# AltimeterFio.net
KiCad netlist of a schematic drawn in EAGLE
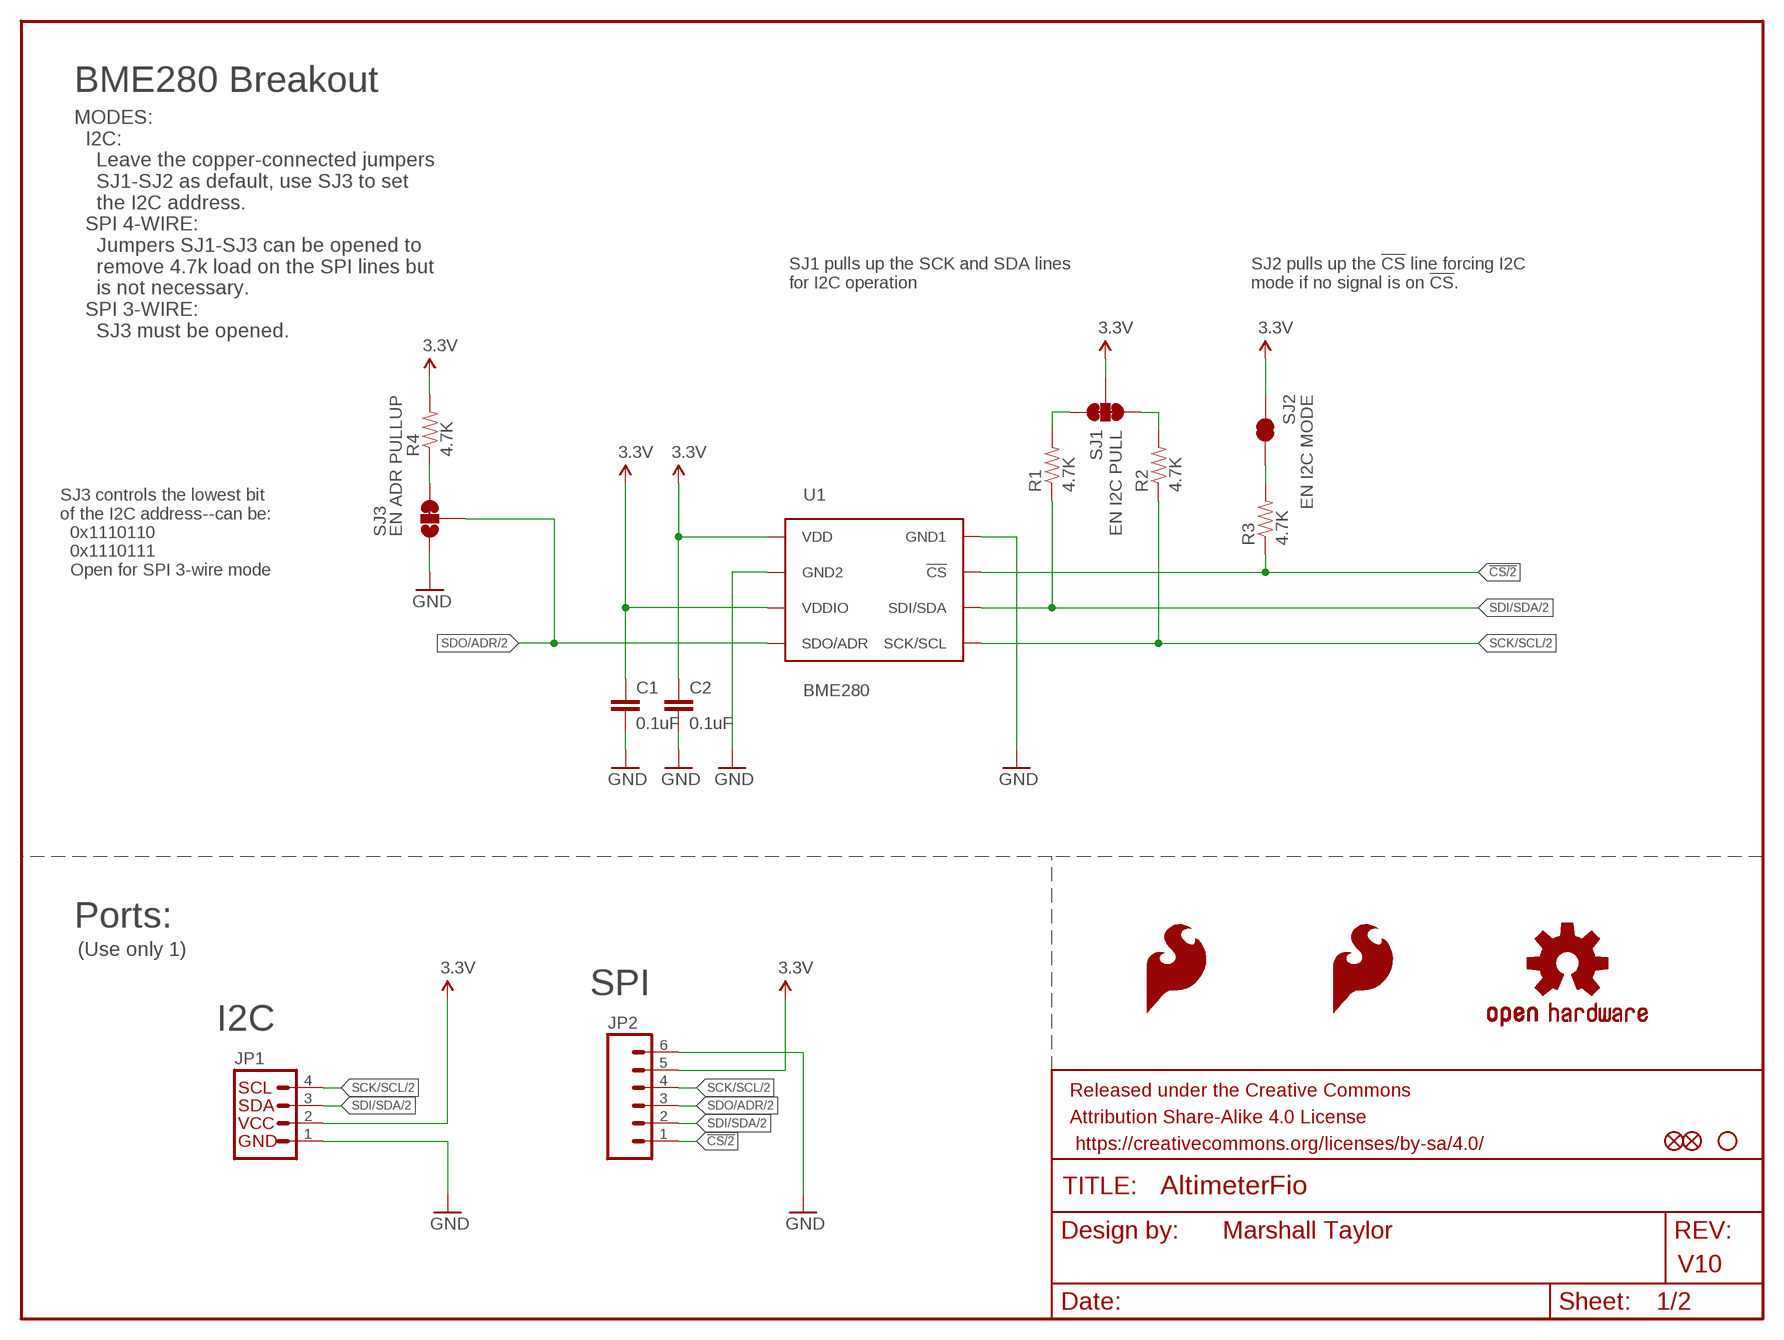
[diagram p0: schematic, sheet 1]
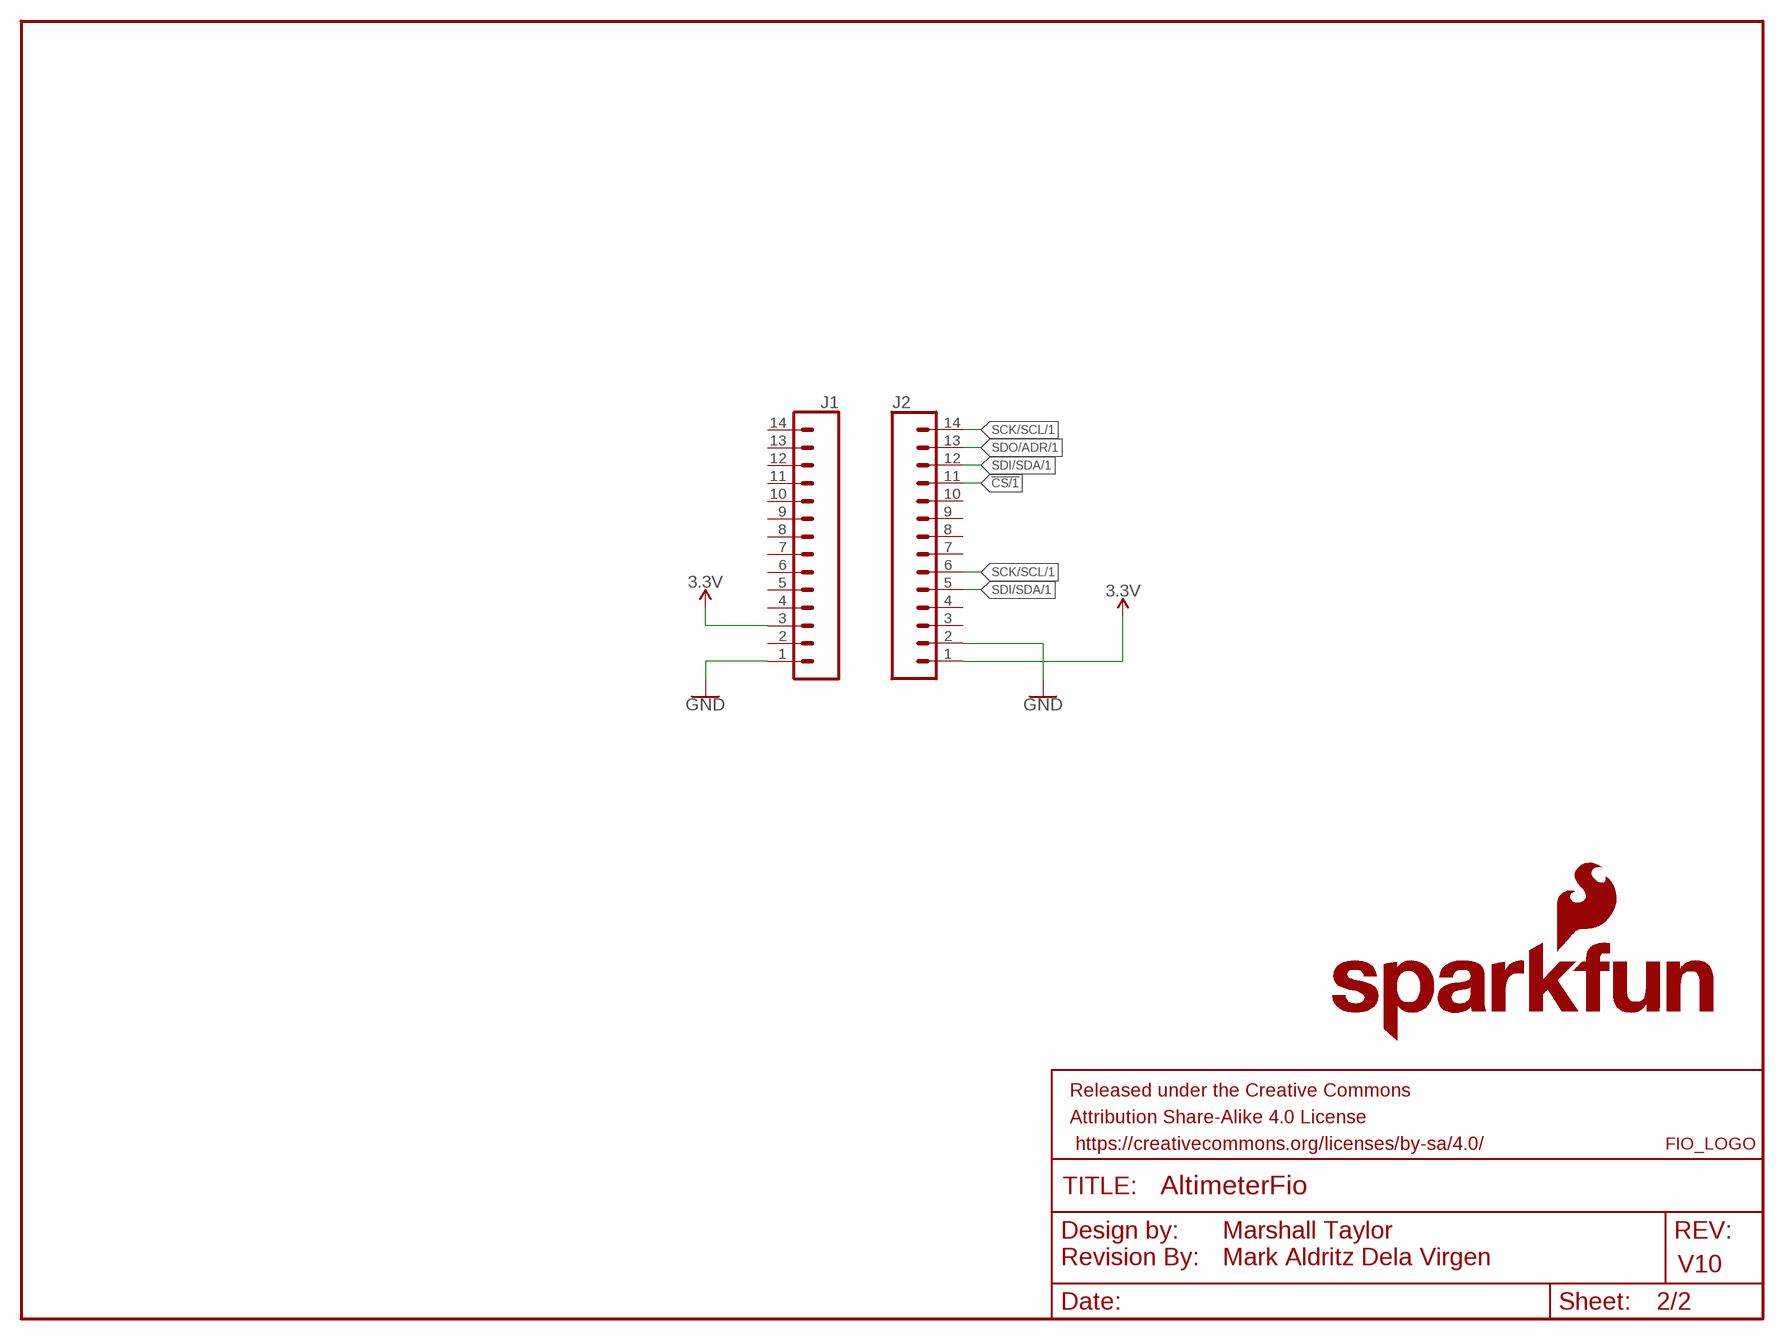
[diagram p1: schematic, sheet 2]

(export (version "E")
  (design (tool "Eeschema 10.0.6"))
  (components
    (comp (ref "C1")
      (value "0.1uF")
      (footprint "eagle-import:0603-CAP")
      (libsource (lib "eagle-import") (part "0.1UF-25V-5%(0603)"))
    )
    (comp (ref "C2")
      (value "0.1uF")
      (footprint "eagle-import:0603-CAP")
      (libsource (lib "eagle-import") (part "0.1UF-25V-5%(0603)"))
    )
    (comp (ref "FID1")
      (value "FIDUCIAL1X2")
      (footprint "eagle-import:FIDUCIAL-1X2")
      (libsource (lib "eagle-import") (part "FIDUCIAL1X2"))
    )
    (comp (ref "FID2")
      (value "FIDUCIAL1X2")
      (footprint "eagle-import:FIDUCIAL-1X2")
      (libsource (lib "eagle-import") (part "FIDUCIAL1X2"))
    )
    (comp (ref "FRAME1")
      (value "FRAME-LETTER")
      (footprint "eagle-import:CREATIVE_COMMONS")
      (libsource (lib "eagle-import") (part "FRAME-LETTER"))
    )
    (comp (ref "JP1")
      (value "I2C_STANDARD_NO_SILK")
      (footprint "eagle-import:1X04_NO_SILK")
      (libsource (lib "eagle-import") (part "I2C_STANDARD_NO_SILK"))
    )
    (comp (ref "JP2")
      (value "M06NO_SILK_FEMALE_PTH")
      (footprint "eagle-import:1X06_NO_SILK")
      (libsource (lib "eagle-import") (part "M06NO_SILK_FEMALE_PTH"))
    )
    (comp (ref "LOGO1")
      (value "SFE_LOGO_FLAME.1_INCH")
      (footprint "eagle-import:SFE_LOGO_FLAME_.1")
      (libsource (lib "eagle-import") (part "SFE_LOGO_FLAME.1_INCH"))
    )
    (comp (ref "LOGO2")
      (value "SFE_LOGO_FLAME.1_INCH")
      (footprint "eagle-import:SFE_LOGO_FLAME_.1")
      (libsource (lib "eagle-import") (part "SFE_LOGO_FLAME.1_INCH"))
    )
    (comp (ref "LOGO3")
      (value "OSHW-LOGOS")
      (footprint "eagle-import:OSHW-LOGO-S")
      (libsource (lib "eagle-import") (part "OSHW-LOGOS"))
    )
    (comp (ref "R1")
      (value "4.7K")
      (footprint "eagle-import:0603-RES")
      (libsource (lib "eagle-import") (part "4.7KOHM-1/10W-1%(0603)"))
    )
    (comp (ref "R2")
      (value "4.7K")
      (footprint "eagle-import:0603-RES")
      (libsource (lib "eagle-import") (part "4.7KOHM-1/10W-1%(0603)"))
    )
    (comp (ref "R3")
      (value "4.7K")
      (footprint "eagle-import:0603-RES")
      (libsource (lib "eagle-import") (part "4.7KOHM-1/10W-1%(0603)"))
    )
    (comp (ref "R4")
      (value "4.7K")
      (footprint "eagle-import:0603-RES")
      (libsource (lib "eagle-import") (part "4.7KOHM-1/10W-1%(0603)"))
    )
    (comp (ref "SJ1")
      (value "EN I2C PULL")
      (footprint "eagle-import:PAD-JUMPER-3-3OF3_NC_BY_TRACE_YES_SILK_FULL_BOX")
      (libsource (lib "eagle-import") (part "JUMPER-PAD-3-NC_BY_TRACE"))
    )
    (comp (ref "SJ2")
      (value "EN I2C MODE")
      (footprint "eagle-import:PAD-JUMPER-2-NC_BY_TRACE_YES_SILK")
      (libsource (lib "eagle-import") (part "JUMPER-PAD-2-NC_BY_TRACE"))
    )
    (comp (ref "SJ3")
      (value "EN ADR PULLUP")
      (footprint "eagle-import:PAD-JUMPER-3-2OF3_NC_BY_TRACE_YES_SILK_FULL_BOX")
      (libsource (lib "eagle-import") (part "JUMPER-PAD-3-2OF3_NC_BY_TRACE_SMALL"))
    )
    (comp (ref "STANDOFF4")
      (value "STAND-OFF")
      (footprint "eagle-import:STAND-OFF")
      (libsource (lib "eagle-import") (part "STAND-OFF"))
    )
    (comp (ref "U1")
      (value "BME280")
      (footprint "eagle-import:BME280_LGA")
      (libsource (lib "eagle-import") (part "BME280"))
    )
    (comp (ref "FRAME2")
      (value "FRAME-LETTERNO_PACKAGE")
      (footprint "eagle-import:DUMMY")
      (fields (field (name "DESIGNER") "Nobody"))
      (libsource (lib "eagle-import") (part "SparkFun-Aesthetics_507_FRAME-LETTERNO_PACKAGE"))
    )
    (comp (ref "J1")
      (value "CONN_14")
      (footprint "eagle-import:1X14")
      (libsource (lib "eagle-import") (part "CONN_14"))
    )
    (comp (ref "J2")
      (value "CONN_14")
      (footprint "eagle-import:1X14")
      (libsource (lib "eagle-import") (part "CONN_14"))
    )
    (comp (ref "LOGO4")
      (value "FIO_LOGOV2")
      (footprint "eagle-import:FIO_LOGO")
      (libsource (lib "eagle-import") (part "FIO_LOGOV2"))
    )
    (comp (ref "LOGO5")
      (value "REVISION")
      (footprint "eagle-import:REVISION")
      (libsource (lib "eagle-import") (part "REVISION"))
    )
    (comp (ref "LOGO6")
      (value "SFE_LOGO_NAME_FLAME.1_INCH")
      (footprint "eagle-import:SFE_LOGO_NAME_FLAME_.1")
      (libsource (lib "eagle-import") (part "SFE_LOGO_NAME_FLAME.1_INCH"))
    )
  )
  (nets
    (net (code "1") (name "3.3V") (class "Default")
      (node (ref "C1") (pin "1") (pinfunction "1_1") (pintype "passive"))
      (node (ref "C2") (pin "1") (pinfunction "1_1") (pintype "passive"))
      (node (ref "J1") (pin "3") (pinfunction "3_3") (pintype "passive"))
      (node (ref "J2") (pin "1") (pinfunction "1_1") (pintype "passive"))
      (node (ref "JP1") (pin "2") (pinfunction "2_2") (pintype "passive"))
      (node (ref "JP2") (pin "5") (pinfunction "5_5") (pintype "passive"))
      (node (ref "R4") (pin "2") (pinfunction "2_2") (pintype "passive"))
      (node (ref "SJ1") (pin "2") (pinfunction "2_2") (pintype "passive"))
      (node (ref "SJ2") (pin "2") (pinfunction "2_2") (pintype "passive"))
      (node (ref "U1") (pin "P$6") (pinfunction "VDDIO_P$6") (pintype "bidirectional"))
      (node (ref "U1") (pin "P$8") (pinfunction "VDD_P$8") (pintype "bidirectional"))
    )
    (net (code "2") (name "GND") (class "Default")
      (node (ref "C1") (pin "2") (pinfunction "2_2") (pintype "passive"))
      (node (ref "C2") (pin "2") (pinfunction "2_2") (pintype "passive"))
      (node (ref "J1") (pin "1") (pinfunction "1_1") (pintype "passive"))
      (node (ref "J2") (pin "2") (pinfunction "2_2") (pintype "passive"))
      (node (ref "JP1") (pin "1") (pinfunction "1_1") (pintype "passive"))
      (node (ref "JP2") (pin "6") (pinfunction "6_6") (pintype "passive"))
      (node (ref "SJ3") (pin "1") (pinfunction "1_1") (pintype "passive"))
      (node (ref "U1") (pin "P$1") (pinfunction "GND1_P$1") (pintype "bidirectional"))
      (node (ref "U1") (pin "P$7") (pinfunction "GND2_P$7") (pintype "bidirectional"))
    )
    (net (code "3") (name "Net-(R1-Pad2)") (class "Default")
      (node (ref "R1") (pin "2") (pinfunction "2_2") (pintype "passive"))
      (node (ref "SJ1") (pin "3") (pinfunction "3_3") (pintype "passive"))
    )
    (net (code "4") (name "Net-(R2-Pad2)") (class "Default")
      (node (ref "R2") (pin "2") (pinfunction "2_2") (pintype "passive"))
      (node (ref "SJ1") (pin "1") (pinfunction "1_1") (pintype "passive"))
    )
    (net (code "5") (name "Net-(R3-Pad2)") (class "Default")
      (node (ref "R3") (pin "2") (pinfunction "2_2") (pintype "passive"))
      (node (ref "SJ2") (pin "1") (pinfunction "1_1") (pintype "passive"))
    )
    (net (code "6") (name "Net-(R4-Pad1)") (class "Default")
      (node (ref "R4") (pin "1") (pinfunction "1_1") (pintype "passive"))
      (node (ref "SJ3") (pin "3") (pinfunction "3_3") (pintype "passive"))
    )
    (net (code "7") (name "SCK{slash}SCL") (class "Default")
      (node (ref "J2") (pin "14") (pinfunction "14_14") (pintype "passive"))
      (node (ref "J2") (pin "6") (pinfunction "6_6") (pintype "passive"))
      (node (ref "JP1") (pin "4") (pinfunction "4_4") (pintype "passive"))
      (node (ref "JP2") (pin "4") (pinfunction "4_4") (pintype "passive"))
      (node (ref "R2") (pin "1") (pinfunction "1_1") (pintype "passive"))
      (node (ref "U1") (pin "P$4") (pinfunction "SCK/SCL_P$4") (pintype "bidirectional"))
    )
    (net (code "8") (name "SDI{slash}SDA") (class "Default")
      (node (ref "J2") (pin "12") (pinfunction "12_12") (pintype "passive"))
      (node (ref "J2") (pin "5") (pinfunction "5_5") (pintype "passive"))
      (node (ref "JP1") (pin "3") (pinfunction "3_3") (pintype "passive"))
      (node (ref "JP2") (pin "2") (pinfunction "2_2") (pintype "passive"))
      (node (ref "R1") (pin "1") (pinfunction "1_1") (pintype "passive"))
      (node (ref "U1") (pin "P$3") (pinfunction "SDI/SDA_P$3") (pintype "bidirectional"))
    )
    (net (code "9") (name "SDO{slash}ADR") (class "Default")
      (node (ref "J2") (pin "13") (pinfunction "13_13") (pintype "passive"))
      (node (ref "JP2") (pin "3") (pinfunction "3_3") (pintype "passive"))
      (node (ref "SJ3") (pin "2") (pinfunction "2_2") (pintype "passive"))
      (node (ref "U1") (pin "P$5") (pinfunction "SDO/ADR_P$5") (pintype "bidirectional"))
    )
    (net (code "10") (name "unconnected-(J1-Pad2)") (class "Default")
      (node (ref "J1") (pin "2") (pinfunction "2_2") (pintype "passive"))
    )
    (net (code "11") (name "unconnected-(J1-Pad4)") (class "Default")
      (node (ref "J1") (pin "4") (pinfunction "4_4") (pintype "passive"))
    )
    (net (code "12") (name "unconnected-(J1-Pad5)") (class "Default")
      (node (ref "J1") (pin "5") (pinfunction "5_5") (pintype "passive"))
    )
    (net (code "13") (name "unconnected-(J1-Pad6)") (class "Default")
      (node (ref "J1") (pin "6") (pinfunction "6_6") (pintype "passive"))
    )
    (net (code "14") (name "unconnected-(J1-Pad7)") (class "Default")
      (node (ref "J1") (pin "7") (pinfunction "7_7") (pintype "passive"))
    )
    (net (code "15") (name "unconnected-(J1-Pad8)") (class "Default")
      (node (ref "J1") (pin "8") (pinfunction "8_8") (pintype "passive"))
    )
    (net (code "16") (name "unconnected-(J1-Pad9)") (class "Default")
      (node (ref "J1") (pin "9") (pinfunction "9_9") (pintype "passive"))
    )
    (net (code "17") (name "unconnected-(J1-Pad10)") (class "Default")
      (node (ref "J1") (pin "10") (pinfunction "10_10") (pintype "passive"))
    )
    (net (code "18") (name "unconnected-(J1-Pad11)") (class "Default")
      (node (ref "J1") (pin "11") (pinfunction "11_11") (pintype "passive"))
    )
    (net (code "19") (name "unconnected-(J1-Pad12)") (class "Default")
      (node (ref "J1") (pin "12") (pinfunction "12_12") (pintype "passive"))
    )
    (net (code "20") (name "unconnected-(J1-Pad13)") (class "Default")
      (node (ref "J1") (pin "13") (pinfunction "13_13") (pintype "passive"))
    )
    (net (code "21") (name "unconnected-(J1-Pad14)") (class "Default")
      (node (ref "J1") (pin "14") (pinfunction "14_14") (pintype "passive"))
    )
    (net (code "22") (name "unconnected-(J2-Pad3)") (class "Default")
      (node (ref "J2") (pin "3") (pinfunction "3_3") (pintype "passive"))
    )
    (net (code "23") (name "unconnected-(J2-Pad4)") (class "Default")
      (node (ref "J2") (pin "4") (pinfunction "4_4") (pintype "passive"))
    )
    (net (code "24") (name "unconnected-(J2-Pad7)") (class "Default")
      (node (ref "J2") (pin "7") (pinfunction "7_7") (pintype "passive"))
    )
    (net (code "25") (name "unconnected-(J2-Pad8)") (class "Default")
      (node (ref "J2") (pin "8") (pinfunction "8_8") (pintype "passive"))
    )
    (net (code "26") (name "unconnected-(J2-Pad9)") (class "Default")
      (node (ref "J2") (pin "9") (pinfunction "9_9") (pintype "passive"))
    )
    (net (code "27") (name "unconnected-(J2-Pad10)") (class "Default")
      (node (ref "J2") (pin "10") (pinfunction "10_10") (pintype "passive"))
    )
    (net (code "28") (name "~{CS}") (class "Default")
      (node (ref "J2") (pin "11") (pinfunction "11_11") (pintype "passive"))
      (node (ref "JP2") (pin "1") (pinfunction "1_1") (pintype "passive"))
      (node (ref "R3") (pin "1") (pinfunction "1_1") (pintype "passive"))
      (node (ref "U1") (pin "P$2") (pinfunction "~{CS}_P$2") (pintype "bidirectional"))
    )
  )
)
